# MIXR_Input_System_-_Buffer.net
KiCad netlist of a schematic drawn in Altium Designer
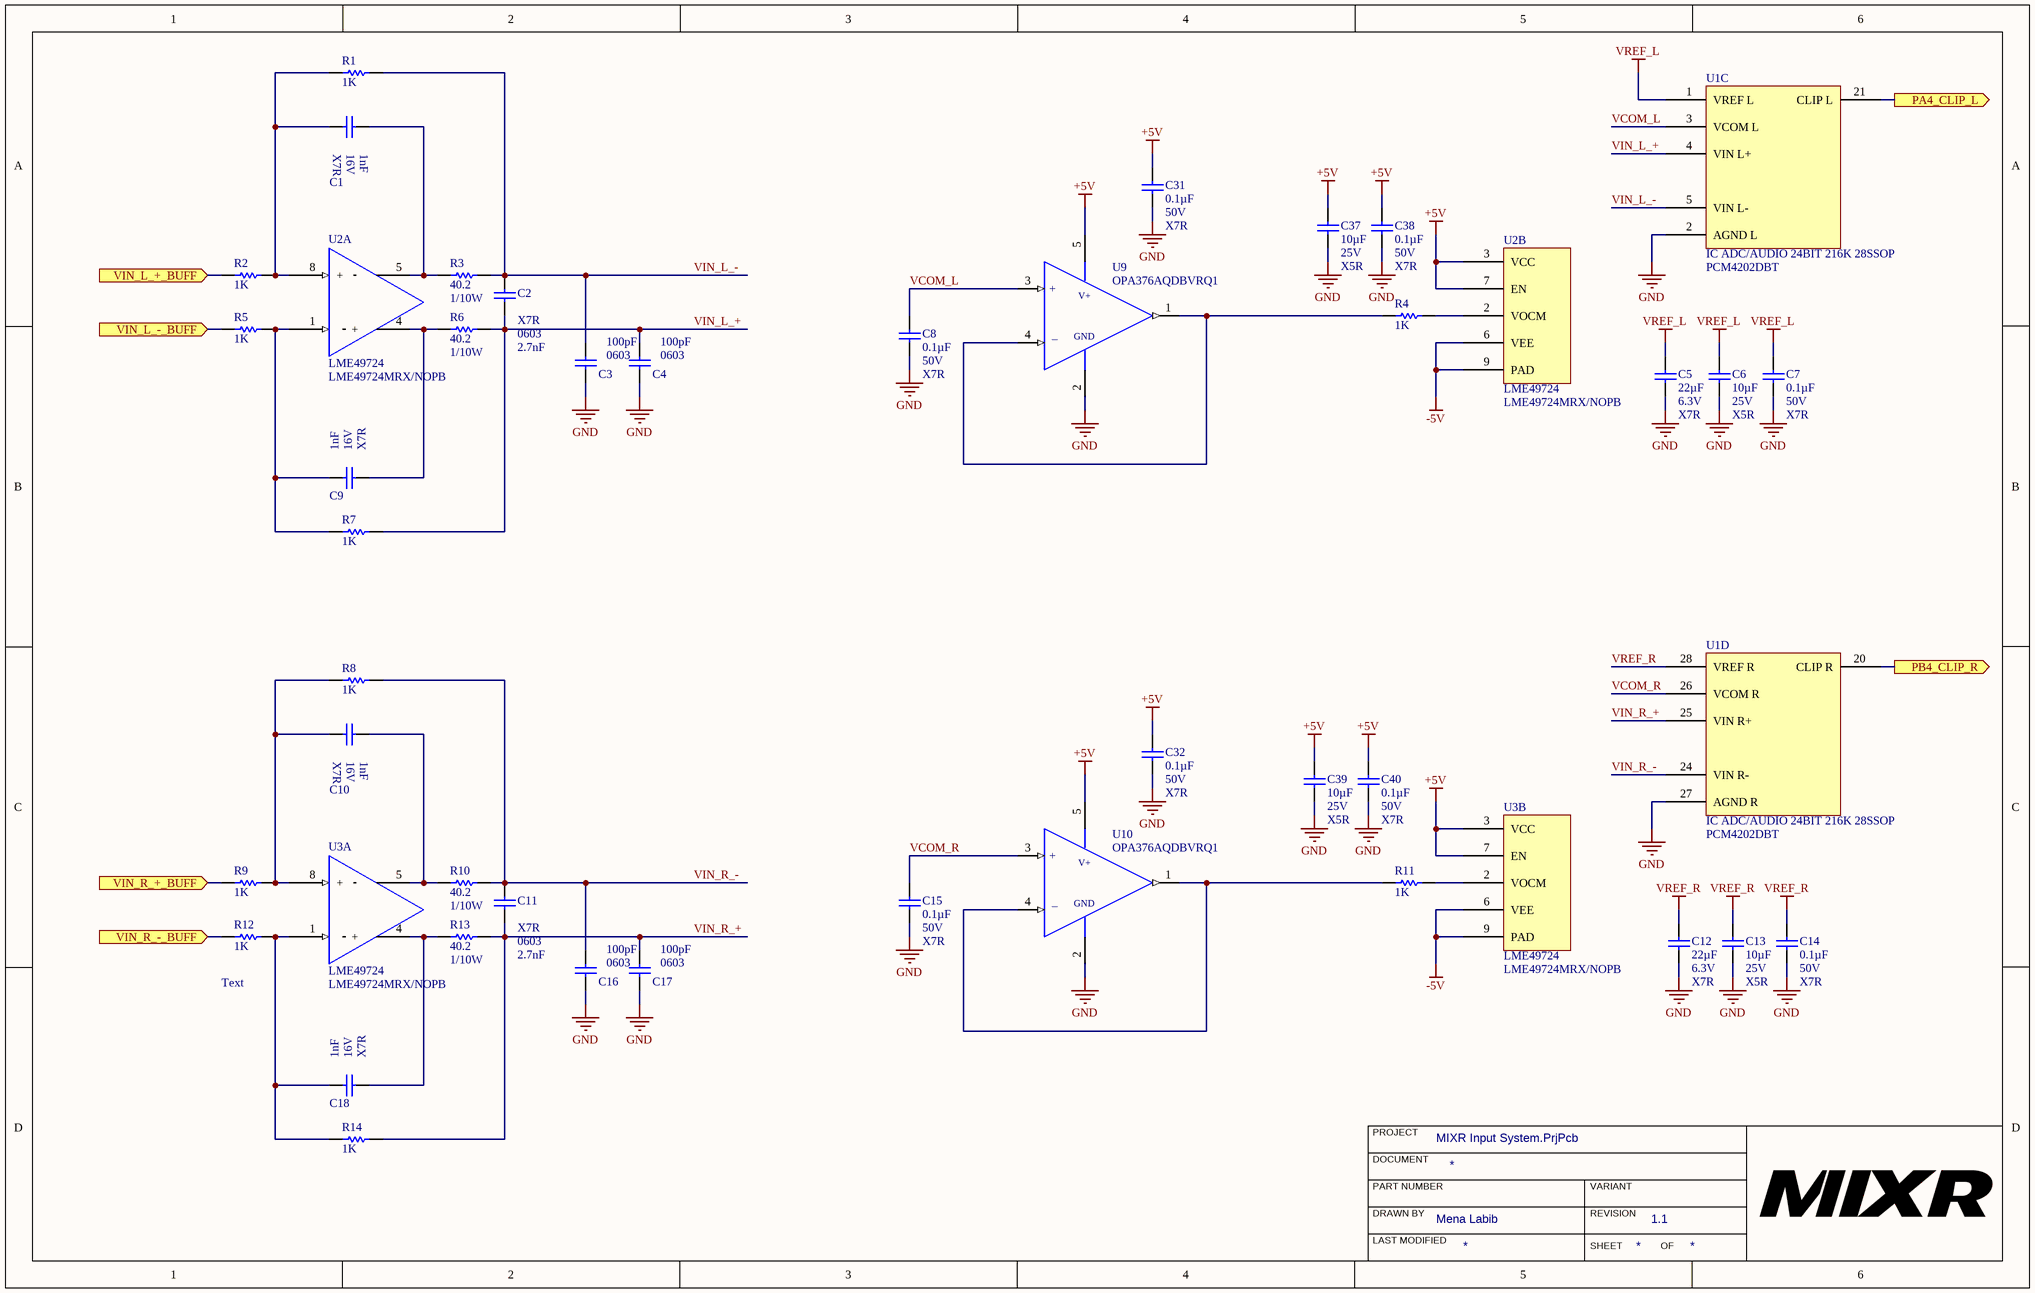
[diagram p0: MIXR Input System - Buffer.SchDoc]

(export (version "E")
  (design (tool "Eeschema 10.0.6"))
  (components
    (comp (ref "C1")
      (value "CAP CER 1NF 16V 10% X7R 0603")
      (footprint "CAP, 0603")
      (description "1000pF ±10% 16V Ceramic Capacitor X7R 0603 (1608 Metric)")
      (fields
        (field (name "MANUFACTURER") "KEMET")
        (field (name "MANUFACTURER PART NUMBER") "C0603C102K4RECAUTO")
      )
      (libsource (lib "Schematic Diagrams") (part "CAP CER 1NF 16V 10% X7R 0603"))
    )
    (comp (ref "C2")
      (value "CAP CER 2700PF 50V X7R 0603")
      (footprint "CAP, 0603")
      (description "2700pF ±10% 50V Ceramic Capacitor X7R 0603 (1608 Metric)")
      (fields
        (field (name "MANUFACTURER") "KEMET")
        (field (name "MANUFACTURER PART NUMBER") "C0603C272K5RACTU")
        (field (name "DIELECTRIC") "X7R")
        (field (name "CASE CODE (IMPERIAL)") "0603")
        (field (name "CAPACITANCE") "2.7nF")
      )
      (libsource (lib "Schematic Diagrams") (part "CAP CER 2700PF 50V X7R 0603"))
    )
    (comp (ref "C3")
      (value "CAP CER 100PF 50V C0G/NP0 0603")
      (footprint "CAP, 0603")
      (description "100pF ±1% 50V Ceramic Capacitor C0G, NP0 0603 (1608 Metric)")
      (fields
        (field (name "MANUFACTURER") "Kyocera AVX")
        (field (name "MANUFACTURER PART NUMBER") "06035A101FAT2A")
        (field (name "CASE CODE (IMPERIAL)") "0603")
        (field (name "CAPACITANCE") "100pF")
      )
      (libsource (lib "Schematic Diagrams") (part "CAP CER 100PF 50V C0G/NP0 0603"))
    )
    (comp (ref "C4")
      (value "CAP CER 100PF 50V C0G/NP0 0603")
      (footprint "CAP, 0603")
      (description "100pF ±1% 50V Ceramic Capacitor C0G, NP0 0603 (1608 Metric)")
      (fields
        (field (name "MANUFACTURER") "Kyocera AVX")
        (field (name "MANUFACTURER PART NUMBER") "06035A101FAT2A")
        (field (name "CASE CODE (IMPERIAL)") "0603")
        (field (name "CAPACITANCE") "100pF")
      )
      (libsource (lib "Schematic Diagrams") (part "CAP CER 100PF 50V C0G/NP0 0603"))
    )
    (comp (ref "C5")
      (value "CAP CER 22UF 6.3V ±10% X7R 1206")
      (footprint "CAP, 1206")
      (description "22µF ±10% 6.3V Ceramic Capacitor X7R 1206 (3216 Metric)")
      (fields
        (field (name "TOLERANCE") "±10%")
        (field (name "CAPACITANCE") "22µF")
        (field (name "VOLTAGE") "6.3V")
        (field (name "TEMPERATURE COEFFICIENT") "X7R")
      )
      (libsource (lib "Schematic Diagrams") (part "CAP CER 22UF 6.3V ±10% X7R 1206"))
    )
    (comp (ref "C6")
      (value "CAP CER 10uF 25V 20% X5R 0603")
      (footprint "CAP, 0603")
      (description "10µF ±20% 25V Ceramic Capacitor X5R 0603 (1608 Metric)")
      (fields
        (field (name "TOLERANCE") "±20%")
        (field (name "CAPACITANCE") "10µF")
        (field (name "VOLTAGE") "25V")
        (field (name "TEMPERATURE COEFFICIENT") "X5R")
      )
      (libsource (lib "Schematic Diagrams") (part "CAP CER 10uF 25V 20% X5R 0603"))
    )
    (comp (ref "C7")
      (value "CAP CER 0.1UF 50V 10% X7R 0603")
      (footprint "CAP, 0603")
      (description "0.10µF ±10% 50V Ceramic Capacitor X7R 0603 (1608 Metric)")
      (fields
        (field (name "TOLERANCE") "±10%")
        (field (name "CAPACITANCE") "0.1µF")
        (field (name "VOLTAGE") "50V")
        (field (name "TEMPERATURE COEFFICIENT") "X7R")
      )
      (libsource (lib "Schematic Diagrams") (part "CAP CER 0.1UF 50V 10% X7R 0603"))
    )
    (comp (ref "C8")
      (value "CAP CER 0.1UF 50V 10% X7R 0603")
      (footprint "CAP, 0603")
      (description "0.10µF ±10% 50V Ceramic Capacitor X7R 0603 (1608 Metric)")
      (fields
        (field (name "TOLERANCE") "±10%")
        (field (name "CAPACITANCE") "0.1µF")
        (field (name "VOLTAGE") "50V")
        (field (name "TEMPERATURE COEFFICIENT") "X7R")
      )
      (libsource (lib "Schematic Diagrams") (part "CAP CER 0.1UF 50V 10% X7R 0603"))
    )
    (comp (ref "C9")
      (value "CAP CER 1NF 16V 10% X7R 0603")
      (footprint "CAP, 0603")
      (description "1000pF ±10% 16V Ceramic Capacitor X7R 0603 (1608 Metric)")
      (fields
        (field (name "MANUFACTURER") "KEMET")
        (field (name "MANUFACTURER PART NUMBER") "C0603C102K4RECAUTO")
      )
      (libsource (lib "Schematic Diagrams") (part "CAP CER 1NF 16V 10% X7R 0603"))
    )
    (comp (ref "C10")
      (value "CAP CER 1NF 16V 10% X7R 0603")
      (footprint "CAP, 0603")
      (description "1000pF ±10% 16V Ceramic Capacitor X7R 0603 (1608 Metric)")
      (fields
        (field (name "MANUFACTURER") "KEMET")
        (field (name "MANUFACTURER PART NUMBER") "C0603C102K4RECAUTO")
      )
      (libsource (lib "Schematic Diagrams") (part "CAP CER 1NF 16V 10% X7R 0603"))
    )
    (comp (ref "C11")
      (value "CAP CER 2700PF 50V X7R 0603")
      (footprint "CAP, 0603")
      (description "2700pF ±10% 50V Ceramic Capacitor X7R 0603 (1608 Metric)")
      (fields
        (field (name "MANUFACTURER") "KEMET")
        (field (name "MANUFACTURER PART NUMBER") "C0603C272K5RACTU")
        (field (name "DIELECTRIC") "X7R")
        (field (name "CASE CODE (IMPERIAL)") "0603")
        (field (name "CAPACITANCE") "2.7nF")
      )
      (libsource (lib "Schematic Diagrams") (part "CAP CER 2700PF 50V X7R 0603"))
    )
    (comp (ref "C12")
      (value "CAP CER 22UF 6.3V ±10% X7R 1206")
      (footprint "CAP, 1206")
      (description "22µF ±10% 6.3V Ceramic Capacitor X7R 1206 (3216 Metric)")
      (fields
        (field (name "TOLERANCE") "±10%")
        (field (name "CAPACITANCE") "22µF")
        (field (name "VOLTAGE") "6.3V")
        (field (name "TEMPERATURE COEFFICIENT") "X7R")
      )
      (libsource (lib "Schematic Diagrams") (part "CAP CER 22UF 6.3V ±10% X7R 1206"))
    )
    (comp (ref "C13")
      (value "CAP CER 10uF 25V 20% X5R 0603")
      (footprint "CAP, 0603")
      (description "10µF ±20% 25V Ceramic Capacitor X5R 0603 (1608 Metric)")
      (fields
        (field (name "TOLERANCE") "±20%")
        (field (name "CAPACITANCE") "10µF")
        (field (name "VOLTAGE") "25V")
        (field (name "TEMPERATURE COEFFICIENT") "X5R")
      )
      (libsource (lib "Schematic Diagrams") (part "CAP CER 10uF 25V 20% X5R 0603"))
    )
    (comp (ref "C14")
      (value "CAP CER 0.1UF 50V 10% X7R 0603")
      (footprint "CAP, 0603")
      (description "0.10µF ±10% 50V Ceramic Capacitor X7R 0603 (1608 Metric)")
      (fields
        (field (name "TOLERANCE") "±10%")
        (field (name "CAPACITANCE") "0.1µF")
        (field (name "VOLTAGE") "50V")
        (field (name "TEMPERATURE COEFFICIENT") "X7R")
      )
      (libsource (lib "Schematic Diagrams") (part "CAP CER 0.1UF 50V 10% X7R 0603"))
    )
    (comp (ref "C15")
      (value "CAP CER 0.1UF 50V 10% X7R 0603")
      (footprint "CAP, 0603")
      (description "0.10µF ±10% 50V Ceramic Capacitor X7R 0603 (1608 Metric)")
      (fields
        (field (name "TOLERANCE") "±10%")
        (field (name "CAPACITANCE") "0.1µF")
        (field (name "VOLTAGE") "50V")
        (field (name "TEMPERATURE COEFFICIENT") "X7R")
      )
      (libsource (lib "Schematic Diagrams") (part "CAP CER 0.1UF 50V 10% X7R 0603"))
    )
    (comp (ref "C16")
      (value "CAP CER 100PF 50V C0G/NP0 0603")
      (footprint "CAP, 0603")
      (description "100pF ±1% 50V Ceramic Capacitor C0G, NP0 0603 (1608 Metric)")
      (fields
        (field (name "MANUFACTURER") "Kyocera AVX")
        (field (name "MANUFACTURER PART NUMBER") "06035A101FAT2A")
        (field (name "CASE CODE (IMPERIAL)") "0603")
        (field (name "CAPACITANCE") "100pF")
      )
      (libsource (lib "Schematic Diagrams") (part "CAP CER 100PF 50V C0G/NP0 0603"))
    )
    (comp (ref "C17")
      (value "CAP CER 100PF 50V C0G/NP0 0603")
      (footprint "CAP, 0603")
      (description "100pF ±1% 50V Ceramic Capacitor C0G, NP0 0603 (1608 Metric)")
      (fields
        (field (name "MANUFACTURER") "Kyocera AVX")
        (field (name "MANUFACTURER PART NUMBER") "06035A101FAT2A")
        (field (name "CASE CODE (IMPERIAL)") "0603")
        (field (name "CAPACITANCE") "100pF")
      )
      (libsource (lib "Schematic Diagrams") (part "CAP CER 100PF 50V C0G/NP0 0603"))
    )
    (comp (ref "C18")
      (value "CAP CER 1NF 16V 10% X7R 0603")
      (footprint "CAP, 0603")
      (description "1000pF ±10% 16V Ceramic Capacitor X7R 0603 (1608 Metric)")
      (fields
        (field (name "MANUFACTURER") "KEMET")
        (field (name "MANUFACTURER PART NUMBER") "C0603C102K4RECAUTO")
      )
      (libsource (lib "Schematic Diagrams") (part "CAP CER 1NF 16V 10% X7R 0603"))
    )
    (comp (ref "C31")
      (value "CAP CER 0.1UF 50V 10% X7R 0603")
      (footprint "CAP, 0603")
      (description "0.10µF ±10% 50V Ceramic Capacitor X7R 0603 (1608 Metric)")
      (fields
        (field (name "TOLERANCE") "±10%")
        (field (name "CAPACITANCE") "0.1µF")
        (field (name "VOLTAGE") "50V")
        (field (name "TEMPERATURE COEFFICIENT") "X7R")
      )
      (libsource (lib "Schematic Diagrams") (part "CAP CER 0.1UF 50V 10% X7R 0603"))
    )
    (comp (ref "C32")
      (value "CAP CER 0.1UF 50V 10% X7R 0603")
      (footprint "CAP, 0603")
      (description "0.10µF ±10% 50V Ceramic Capacitor X7R 0603 (1608 Metric)")
      (fields
        (field (name "TOLERANCE") "±10%")
        (field (name "CAPACITANCE") "0.1µF")
        (field (name "VOLTAGE") "50V")
        (field (name "TEMPERATURE COEFFICIENT") "X7R")
      )
      (libsource (lib "Schematic Diagrams") (part "CAP CER 0.1UF 50V 10% X7R 0603"))
    )
    (comp (ref "C37")
      (value "CAP CER 10uF 25V 20% X5R 0603")
      (footprint "CAP, 0603")
      (description "10µF ±20% 25V Ceramic Capacitor X5R 0603 (1608 Metric)")
      (fields
        (field (name "TOLERANCE") "±20%")
        (field (name "CAPACITANCE") "10µF")
        (field (name "VOLTAGE") "25V")
        (field (name "TEMPERATURE COEFFICIENT") "X5R")
      )
      (libsource (lib "Schematic Diagrams") (part "CAP CER 10uF 25V 20% X5R 0603"))
    )
    (comp (ref "C38")
      (value "CAP CER 0.1UF 50V 10% X7R 0603")
      (footprint "CAP, 0603")
      (description "0.10µF ±10% 50V Ceramic Capacitor X7R 0603 (1608 Metric)")
      (fields
        (field (name "TOLERANCE") "±10%")
        (field (name "CAPACITANCE") "0.1µF")
        (field (name "VOLTAGE") "50V")
        (field (name "TEMPERATURE COEFFICIENT") "X7R")
      )
      (libsource (lib "Schematic Diagrams") (part "CAP CER 0.1UF 50V 10% X7R 0603"))
    )
    (comp (ref "C39")
      (value "CAP CER 10uF 25V 20% X5R 0603")
      (footprint "CAP, 0603")
      (description "10µF ±20% 25V Ceramic Capacitor X5R 0603 (1608 Metric)")
      (fields
        (field (name "TOLERANCE") "±20%")
        (field (name "CAPACITANCE") "10µF")
        (field (name "VOLTAGE") "25V")
        (field (name "TEMPERATURE COEFFICIENT") "X5R")
      )
      (libsource (lib "Schematic Diagrams") (part "CAP CER 10uF 25V 20% X5R 0603"))
    )
    (comp (ref "C40")
      (value "CAP CER 0.1UF 50V 10% X7R 0603")
      (footprint "CAP, 0603")
      (description "0.10µF ±10% 50V Ceramic Capacitor X7R 0603 (1608 Metric)")
      (fields
        (field (name "TOLERANCE") "±10%")
        (field (name "CAPACITANCE") "0.1µF")
        (field (name "VOLTAGE") "50V")
        (field (name "TEMPERATURE COEFFICIENT") "X7R")
      )
      (libsource (lib "Schematic Diagrams") (part "CAP CER 0.1UF 50V 10% X7R 0603"))
    )
    (comp (ref "R1")
      (value "1K")
      (footprint "RES, 0603")
      (description "1k Ohm ±5% 0.1W, 1/10W Chip Resistor 0603 (1608 Metric)")
      (fields
        (field (name "MANUFACTURER") "Yageo")
        (field (name "MANUFACTURER PART NUMBER") "RC0603JR-071KL")
      )
      (libsource (lib "altium-import") (part "root_1_RES 1K OHM 5% 1/10W 0603_"))
    )
    (comp (ref "R2")
      (value "1K")
      (footprint "RES, 0603")
      (description "1k Ohm ±5% 0.1W, 1/10W Chip Resistor 0603 (1608 Metric)")
      (fields
        (field (name "MANUFACTURER") "Yageo")
        (field (name "MANUFACTURER PART NUMBER") "RC0603JR-071KL")
      )
      (libsource (lib "Schematic Diagrams") (part "RES 1K OHM 5% 1/10W 0603"))
    )
    (comp (ref "R3")
      (value "RES 40.2 OHM 0.5% 1/10W 0603")
      (footprint "RES, 0603")
      (description "RES SMD 40.2 OHM 0.5% 1/10W 0603")
      (fields
        (field (name "TOLERANCE") "±0.5%")
        (field (name "RESISTANCE") "40.2")
        (field (name "POWER") "1/10W")
      )
      (libsource (lib "Schematic Diagrams") (part "RES 40.2 OHM 0.5% 1/10W 0603"))
    )
    (comp (ref "R4")
      (value "1K")
      (footprint "RES, 0603")
      (description "1k Ohm ±5% 0.1W, 1/10W Chip Resistor 0603 (1608 Metric)")
      (fields
        (field (name "MANUFACTURER") "Yageo")
        (field (name "MANUFACTURER PART NUMBER") "RC0603JR-071KL")
      )
      (libsource (lib "Schematic Diagrams") (part "RES 1K OHM 5% 1/10W 0603"))
    )
    (comp (ref "R5")
      (value "1K")
      (footprint "RES, 0603")
      (description "1k Ohm ±5% 0.1W, 1/10W Chip Resistor 0603 (1608 Metric)")
      (fields
        (field (name "MANUFACTURER") "Yageo")
        (field (name "MANUFACTURER PART NUMBER") "RC0603JR-071KL")
      )
      (libsource (lib "Schematic Diagrams") (part "RES 1K OHM 5% 1/10W 0603"))
    )
    (comp (ref "R6")
      (value "RES 40.2 OHM 0.5% 1/10W 0603")
      (footprint "RES, 0603")
      (description "RES SMD 40.2 OHM 0.5% 1/10W 0603")
      (fields
        (field (name "TOLERANCE") "±0.5%")
        (field (name "RESISTANCE") "40.2")
        (field (name "POWER") "1/10W")
      )
      (libsource (lib "Schematic Diagrams") (part "RES 40.2 OHM 0.5% 1/10W 0603"))
    )
    (comp (ref "R7")
      (value "1K")
      (footprint "RES, 0603")
      (description "1k Ohm ±5% 0.1W, 1/10W Chip Resistor 0603 (1608 Metric)")
      (fields
        (field (name "MANUFACTURER") "Yageo")
        (field (name "MANUFACTURER PART NUMBER") "RC0603JR-071KL")
      )
      (libsource (lib "altium-import") (part "root_1_RES 1K OHM 5% 1/10W 0603_"))
    )
    (comp (ref "R8")
      (value "1K")
      (footprint "RES, 0603")
      (description "1k Ohm ±5% 0.1W, 1/10W Chip Resistor 0603 (1608 Metric)")
      (fields
        (field (name "MANUFACTURER") "Yageo")
        (field (name "MANUFACTURER PART NUMBER") "RC0603JR-071KL")
      )
      (libsource (lib "altium-import") (part "root_1_RES 1K OHM 5% 1/10W 0603_"))
    )
    (comp (ref "R9")
      (value "1K")
      (footprint "RES, 0603")
      (description "1k Ohm ±5% 0.1W, 1/10W Chip Resistor 0603 (1608 Metric)")
      (fields
        (field (name "MANUFACTURER") "Yageo")
        (field (name "MANUFACTURER PART NUMBER") "RC0603JR-071KL")
      )
      (libsource (lib "Schematic Diagrams") (part "RES 1K OHM 5% 1/10W 0603"))
    )
    (comp (ref "R10")
      (value "RES 40.2 OHM 0.5% 1/10W 0603")
      (footprint "RES, 0603")
      (description "RES SMD 40.2 OHM 0.5% 1/10W 0603")
      (fields
        (field (name "TOLERANCE") "±0.5%")
        (field (name "RESISTANCE") "40.2")
        (field (name "POWER") "1/10W")
      )
      (libsource (lib "Schematic Diagrams") (part "RES 40.2 OHM 0.5% 1/10W 0603"))
    )
    (comp (ref "R11")
      (value "1K")
      (footprint "RES, 0603")
      (description "1k Ohm ±5% 0.1W, 1/10W Chip Resistor 0603 (1608 Metric)")
      (fields
        (field (name "MANUFACTURER") "Yageo")
        (field (name "MANUFACTURER PART NUMBER") "RC0603JR-071KL")
      )
      (libsource (lib "Schematic Diagrams") (part "RES 1K OHM 5% 1/10W 0603"))
    )
    (comp (ref "R12")
      (value "1K")
      (footprint "RES, 0603")
      (description "1k Ohm ±5% 0.1W, 1/10W Chip Resistor 0603 (1608 Metric)")
      (fields
        (field (name "MANUFACTURER") "Yageo")
        (field (name "MANUFACTURER PART NUMBER") "RC0603JR-071KL")
      )
      (libsource (lib "Schematic Diagrams") (part "RES 1K OHM 5% 1/10W 0603"))
    )
    (comp (ref "R13")
      (value "RES 40.2 OHM 0.5% 1/10W 0603")
      (footprint "RES, 0603")
      (description "RES SMD 40.2 OHM 0.5% 1/10W 0603")
      (fields
        (field (name "TOLERANCE") "±0.5%")
        (field (name "RESISTANCE") "40.2")
        (field (name "POWER") "1/10W")
      )
      (libsource (lib "Schematic Diagrams") (part "RES 40.2 OHM 0.5% 1/10W 0603"))
    )
    (comp (ref "R14")
      (value "1K")
      (footprint "RES, 0603")
      (description "1k Ohm ±5% 0.1W, 1/10W Chip Resistor 0603 (1608 Metric)")
      (fields
        (field (name "MANUFACTURER") "Yageo")
        (field (name "MANUFACTURER PART NUMBER") "RC0603JR-071KL")
      )
      (libsource (lib "altium-import") (part "root_1_RES 1K OHM 5% 1/10W 0603_"))
    )
    (comp (ref "U1")
      (value "IC ADC/AUDIO 24BIT 216K 28SSOP")
      (footprint "IC ADC 24 BIT AUDIO 216 KHZ SSOP-28")
      (description "ADC, Audio 24 bit 216k DSP, PCM 28-SSOP")
      (fields
        (field (name "MANUFACTURER") "Texas Instruments")
        (field (name "MANUFACTURER PART NUMBER") "PCM4202DBT")
      )
      (libsource (lib "Schematic Diagrams") (part "IC ADC 24 BIT AUDIO 216KHZ SSOP-28"))
    )
    (comp (ref "U2")
      (value "LME49724")
      (footprint "IC OP AMP AUDIO LME49724 8-SOIC")
      (description "Audio Amplifier 1 Circuit Differential 8-SO PowerPad")
      (fields
        (field (name "MANUFACTURER") "TI National Semiconductor")
        (field (name "MANUFACTURER PART NUMBER") "LME49724MRX/NOPB")
      )
      (libsource (lib "Schematic Diagrams") (part "IC OP AMP AUDIO LME49724 8-SOIC"))
    )
    (comp (ref "U3")
      (value "LME49724")
      (footprint "IC OP AMP AUDIO LME49724 8-SOIC")
      (description "Audio Amplifier 1 Circuit Differential 8-SO PowerPad")
      (fields
        (field (name "MANUFACTURER") "TI National Semiconductor")
        (field (name "MANUFACTURER PART NUMBER") "LME49724MRX/NOPB")
      )
      (libsource (lib "Schematic Diagrams") (part "IC OP AMP AUDIO LME49724 8-SOIC"))
    )
    (comp (ref "U9")
      (value "IC OP AMP GEN PURPOSE RR 5.5MHZ SOT-23-5")
      (footprint "IC OP AMP GP RR 10MHZ SOT-23-5")
      (description "General Purpose Amplifier 1 Circuit Rail-to-Rail SOT-23-5")
      (fields
        (field (name "MANUFACTURER") "Texas Instruments")
        (field (name "MANUFACTURER PART NUMBER") "OPA376AQDBVRQ1")
      )
      (libsource (lib "Schematic Diagrams") (part "IC OP AMP GEN PURPOSE RR 5.5MHZ SOT-23-5"))
    )
    (comp (ref "U10")
      (value "IC OP AMP GEN PURPOSE RR 5.5MHZ SOT-23-5")
      (footprint "IC OP AMP GP RR 10MHZ SOT-23-5")
      (description "General Purpose Amplifier 1 Circuit Rail-to-Rail SOT-23-5")
      (fields
        (field (name "MANUFACTURER") "Texas Instruments")
        (field (name "MANUFACTURER PART NUMBER") "OPA376AQDBVRQ1")
      )
      (libsource (lib "Schematic Diagrams") (part "IC OP AMP GEN PURPOSE RR 5.5MHZ SOT-23-5"))
    )
  )
  (nets
    (net (code "1") (name "+5V") (class "Default")
      (node (ref "C31") (pin "1") (pinfunction "1_1") (pintype "passive"))
      (node (ref "C32") (pin "1") (pinfunction "1_1") (pintype "passive"))
      (node (ref "C37") (pin "1") (pinfunction "1_1") (pintype "passive"))
      (node (ref "C38") (pin "1") (pinfunction "1_1") (pintype "passive"))
      (node (ref "C39") (pin "1") (pinfunction "1_1") (pintype "passive"))
      (node (ref "C40") (pin "1") (pinfunction "1_1") (pintype "passive"))
      (node (ref "U10") (pin "5") (pinfunction "VDD_5") (pintype "power_in"))
      (node (ref "U2") (pin "3") (pinfunction "VCC_3") (pintype "passive"))
      (node (ref "U2") (pin "7") (pinfunction "EN_7") (pintype "passive"))
      (node (ref "U3") (pin "3") (pinfunction "VCC_3") (pintype "passive"))
      (node (ref "U3") (pin "7") (pinfunction "EN_7") (pintype "passive"))
      (node (ref "U9") (pin "5") (pinfunction "VDD_5") (pintype "power_in"))
    )
    (net (code "2") (name "-5V") (class "Default")
      (node (ref "U2") (pin "6") (pinfunction "VEE_6") (pintype "passive"))
      (node (ref "U2") (pin "9") (pinfunction "PAD_9") (pintype "passive"))
      (node (ref "U3") (pin "6") (pinfunction "VEE_6") (pintype "passive"))
      (node (ref "U3") (pin "9") (pinfunction "PAD_9") (pintype "passive"))
    )
    (net (code "3") (name "/PA4_CLIP_L") (class "Default")
      (node (ref "U1") (pin "21") (pinfunction "CLIP_L_21") (pintype "passive"))
    )
    (net (code "4") (name "/PB4_CLIP_R") (class "Default")
      (node (ref "U1") (pin "20") (pinfunction "CLIP_R_20") (pintype "passive"))
    )
    (net (code "5") (name "/VCOM_L") (class "Default")
      (node (ref "C8") (pin "1") (pinfunction "1_1") (pintype "passive"))
      (node (ref "U1") (pin "3") (pinfunction "VCOM_L_3") (pintype "passive"))
      (node (ref "U9") (pin "3") (pinfunction "+IN_3") (pintype "input"))
    )
    (net (code "6") (name "/VCOM_R") (class "Default")
      (node (ref "C15") (pin "1") (pinfunction "1_1") (pintype "passive"))
      (node (ref "U1") (pin "26") (pinfunction "VCOM_R_26") (pintype "passive"))
      (node (ref "U10") (pin "3") (pinfunction "+IN_3") (pintype "input"))
    )
    (net (code "7") (name "/VIN_L_+") (class "Default")
      (node (ref "C2") (pin "2") (pinfunction "2_2") (pintype "passive"))
      (node (ref "C4") (pin "1") (pinfunction "1_1") (pintype "passive"))
      (node (ref "R6") (pin "2") (pinfunction "2_2") (pintype "passive"))
      (node (ref "R7") (pin "2") (pinfunction "2_2") (pintype "passive"))
      (node (ref "U1") (pin "4") (pinfunction "VIN_L+_4") (pintype "passive"))
    )
    (net (code "8") (name "/VIN_L_+_BUFF") (class "Default")
      (node (ref "R2") (pin "1") (pinfunction "1_1") (pintype "passive"))
    )
    (net (code "9") (name "/VIN_L_-") (class "Default")
      (node (ref "C2") (pin "1") (pinfunction "1_1") (pintype "passive"))
      (node (ref "C3") (pin "1") (pinfunction "1_1") (pintype "passive"))
      (node (ref "R1") (pin "2") (pinfunction "2_2") (pintype "passive"))
      (node (ref "R3") (pin "2") (pinfunction "2_2") (pintype "passive"))
      (node (ref "U1") (pin "5") (pinfunction "VIN_L-_5") (pintype "passive"))
    )
    (net (code "10") (name "/VIN_L_-_BUFF") (class "Default")
      (node (ref "R5") (pin "1") (pinfunction "1_1") (pintype "passive"))
    )
    (net (code "11") (name "/VIN_R_+") (class "Default")
      (node (ref "C11") (pin "2") (pinfunction "2_2") (pintype "passive"))
      (node (ref "C17") (pin "1") (pinfunction "1_1") (pintype "passive"))
      (node (ref "R13") (pin "2") (pinfunction "2_2") (pintype "passive"))
      (node (ref "R14") (pin "2") (pinfunction "2_2") (pintype "passive"))
      (node (ref "U1") (pin "25") (pinfunction "VIN_R+_25") (pintype "passive"))
    )
    (net (code "12") (name "/VIN_R_+_BUFF") (class "Default")
      (node (ref "R9") (pin "1") (pinfunction "1_1") (pintype "passive"))
    )
    (net (code "13") (name "/VIN_R_-") (class "Default")
      (node (ref "C11") (pin "1") (pinfunction "1_1") (pintype "passive"))
      (node (ref "C16") (pin "1") (pinfunction "1_1") (pintype "passive"))
      (node (ref "R10") (pin "2") (pinfunction "2_2") (pintype "passive"))
      (node (ref "R8") (pin "2") (pinfunction "2_2") (pintype "passive"))
      (node (ref "U1") (pin "24") (pinfunction "VIN_R-_24") (pintype "passive"))
    )
    (net (code "14") (name "/VIN_R_-_BUFF") (class "Default")
      (node (ref "R12") (pin "1") (pinfunction "1_1") (pintype "passive"))
    )
    (net (code "15") (name "GND") (class "Default")
      (node (ref "C12") (pin "2") (pinfunction "2_2") (pintype "passive"))
      (node (ref "C13") (pin "2") (pinfunction "2_2") (pintype "passive"))
      (node (ref "C14") (pin "2") (pinfunction "2_2") (pintype "passive"))
      (node (ref "C15") (pin "2") (pinfunction "2_2") (pintype "passive"))
      (node (ref "C16") (pin "2") (pinfunction "2_2") (pintype "passive"))
      (node (ref "C17") (pin "2") (pinfunction "2_2") (pintype "passive"))
      (node (ref "C3") (pin "2") (pinfunction "2_2") (pintype "passive"))
      (node (ref "C31") (pin "2") (pinfunction "2_2") (pintype "passive"))
      (node (ref "C32") (pin "2") (pinfunction "2_2") (pintype "passive"))
      (node (ref "C37") (pin "2") (pinfunction "2_2") (pintype "passive"))
      (node (ref "C38") (pin "2") (pinfunction "2_2") (pintype "passive"))
      (node (ref "C39") (pin "2") (pinfunction "2_2") (pintype "passive"))
      (node (ref "C4") (pin "2") (pinfunction "2_2") (pintype "passive"))
      (node (ref "C40") (pin "2") (pinfunction "2_2") (pintype "passive"))
      (node (ref "C5") (pin "2") (pinfunction "2_2") (pintype "passive"))
      (node (ref "C6") (pin "2") (pinfunction "2_2") (pintype "passive"))
      (node (ref "C7") (pin "2") (pinfunction "2_2") (pintype "passive"))
      (node (ref "C8") (pin "2") (pinfunction "2_2") (pintype "passive"))
      (node (ref "U1") (pin "2") (pinfunction "AGND_L_2") (pintype "passive"))
      (node (ref "U1") (pin "27") (pinfunction "AGND_R_27") (pintype "passive"))
      (node (ref "U10") (pin "2") (pinfunction "VSS_2") (pintype "power_in"))
      (node (ref "U9") (pin "2") (pinfunction "VSS_2") (pintype "power_in"))
    )
    (net (code "16") (name "Net-(C1-Pad1)") (class "Default")
      (node (ref "C1") (pin "1") (pinfunction "1_1") (pintype "passive"))
      (node (ref "R3") (pin "1") (pinfunction "1_1") (pintype "passive"))
      (node (ref "U2") (pin "5") (pinfunction "-_5") (pintype "passive"))
    )
    (net (code "17") (name "Net-(C1-Pad2)") (class "Default")
      (node (ref "C1") (pin "2") (pinfunction "2_2") (pintype "passive"))
      (node (ref "R1") (pin "1") (pinfunction "1_1") (pintype "passive"))
      (node (ref "R2") (pin "2") (pinfunction "2_2") (pintype "passive"))
      (node (ref "U2") (pin "8") (pinfunction "+_8") (pintype "input"))
    )
    (net (code "18") (name "Net-(C9-Pad1)") (class "Default")
      (node (ref "C9") (pin "1") (pinfunction "1_1") (pintype "passive"))
      (node (ref "R5") (pin "2") (pinfunction "2_2") (pintype "passive"))
      (node (ref "R7") (pin "1") (pinfunction "1_1") (pintype "passive"))
      (node (ref "U2") (pin "1") (pinfunction "-_1") (pintype "input"))
    )
    (net (code "19") (name "Net-(C9-Pad2)") (class "Default")
      (node (ref "C9") (pin "2") (pinfunction "2_2") (pintype "passive"))
      (node (ref "R6") (pin "1") (pinfunction "1_1") (pintype "passive"))
      (node (ref "U2") (pin "4") (pinfunction "+_4") (pintype "passive"))
    )
    (net (code "20") (name "Net-(C10-Pad1)") (class "Default")
      (node (ref "C10") (pin "1") (pinfunction "1_1") (pintype "passive"))
      (node (ref "R10") (pin "1") (pinfunction "1_1") (pintype "passive"))
      (node (ref "U3") (pin "5") (pinfunction "-_5") (pintype "passive"))
    )
    (net (code "21") (name "Net-(C10-Pad2)") (class "Default")
      (node (ref "C10") (pin "2") (pinfunction "2_2") (pintype "passive"))
      (node (ref "R8") (pin "1") (pinfunction "1_1") (pintype "passive"))
      (node (ref "R9") (pin "2") (pinfunction "2_2") (pintype "passive"))
      (node (ref "U3") (pin "8") (pinfunction "+_8") (pintype "input"))
    )
    (net (code "22") (name "Net-(C18-Pad1)") (class "Default")
      (node (ref "C18") (pin "1") (pinfunction "1_1") (pintype "passive"))
      (node (ref "R12") (pin "2") (pinfunction "2_2") (pintype "passive"))
      (node (ref "R14") (pin "1") (pinfunction "1_1") (pintype "passive"))
      (node (ref "U3") (pin "1") (pinfunction "-_1") (pintype "input"))
    )
    (net (code "23") (name "Net-(C18-Pad2)") (class "Default")
      (node (ref "C18") (pin "2") (pinfunction "2_2") (pintype "passive"))
      (node (ref "R13") (pin "1") (pinfunction "1_1") (pintype "passive"))
      (node (ref "U3") (pin "4") (pinfunction "+_4") (pintype "passive"))
    )
    (net (code "24") (name "Net-(U2B-VOCM)") (class "Default")
      (node (ref "R4") (pin "2") (pinfunction "2_2") (pintype "passive"))
      (node (ref "U2") (pin "2") (pinfunction "VOCM_2") (pintype "passive"))
    )
    (net (code "25") (name "Net-(U3B-VOCM)") (class "Default")
      (node (ref "R11") (pin "2") (pinfunction "2_2") (pintype "passive"))
      (node (ref "U3") (pin "2") (pinfunction "VOCM_2") (pintype "passive"))
    )
    (net (code "26") (name "Net-(U9--IN)") (class "Default")
      (node (ref "R4") (pin "1") (pinfunction "1_1") (pintype "passive"))
      (node (ref "U9") (pin "1") (pinfunction "OUTPUT_1") (pintype "output"))
      (node (ref "U9") (pin "4") (pinfunction "-IN_4") (pintype "input"))
    )
    (net (code "27") (name "Net-(U10--IN)") (class "Default")
      (node (ref "R11") (pin "1") (pinfunction "1_1") (pintype "passive"))
      (node (ref "U10") (pin "1") (pinfunction "OUTPUT_1") (pintype "output"))
      (node (ref "U10") (pin "4") (pinfunction "-IN_4") (pintype "input"))
    )
    (net (code "28") (name "VREF_L") (class "Default")
      (node (ref "C5") (pin "1") (pinfunction "1_1") (pintype "passive"))
      (node (ref "C6") (pin "1") (pinfunction "1_1") (pintype "passive"))
      (node (ref "C7") (pin "1") (pinfunction "1_1") (pintype "passive"))
      (node (ref "U1") (pin "1") (pinfunction "VREF_L_1") (pintype "passive"))
    )
    (net (code "29") (name "VREF_R") (class "Default")
      (node (ref "C12") (pin "1") (pinfunction "1_1") (pintype "passive"))
      (node (ref "C13") (pin "1") (pinfunction "1_1") (pintype "passive"))
      (node (ref "C14") (pin "1") (pinfunction "1_1") (pintype "passive"))
      (node (ref "U1") (pin "28") (pinfunction "VREF_R_28") (pintype "passive"))
    )
  )
)
